# breakout_board_M4.net
KiCad netlist of a schematic drawn in Altium Designer
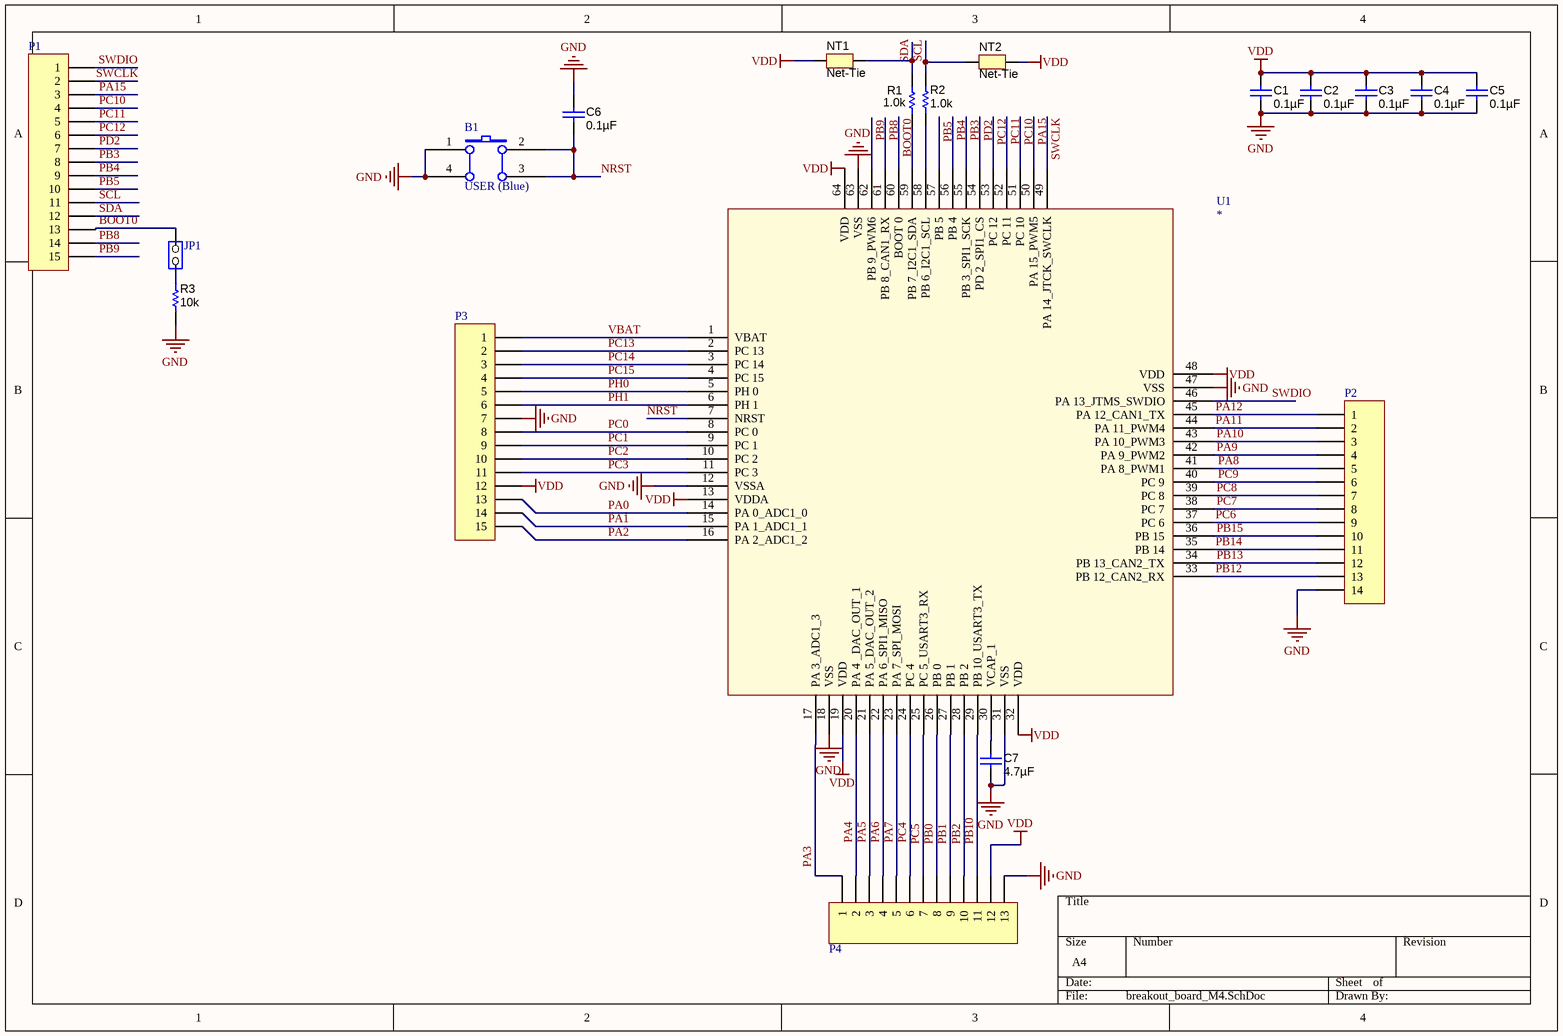
[diagram p0: breakout_board_M4.SchDoc]

(export (version "E")
  (design (tool "Eeschema 10.0.6"))
  (components
    (comp (ref "B1")
      (value "USER (Blue)")
      (footprint "PB-6X6mm-Blue")
      (description "SE PUSHBUTTON")
      (libsource (lib "MB1137") (part "SW PUSHBUTTON"))
    )
    (comp (ref "C1")
      (value "C0603C104K8RACTU")
      (footprint "0603L")
      (description "CAP, CERM, 0.1 µF, 10 V, +/- 10%, X7R, 0603")
      (fields
        (field (name "MANUFACTURER") "Kemet")
        (field (name "VALUEDISPLAYED") "0.1µF")
        (field (name "PUBLISHER") "Texas Instruments")
      )
      (libsource (lib "MDBU014A") (part "C0603C104K8RACTU"))
    )
    (comp (ref "C2")
      (value "C0603C104K8RACTU")
      (footprint "0603L")
      (description "CAP, CERM, 0.1 µF, 10 V, +/- 10%, X7R, 0603")
      (fields
        (field (name "MANUFACTURER") "Kemet")
        (field (name "VALUEDISPLAYED") "0.1µF")
        (field (name "PUBLISHER") "Texas Instruments")
      )
      (libsource (lib "MDBU014A") (part "C0603C104K8RACTU"))
    )
    (comp (ref "C3")
      (value "C0603C104K8RACTU")
      (footprint "0603L")
      (description "CAP, CERM, 0.1 µF, 10 V, +/- 10%, X7R, 0603")
      (fields
        (field (name "MANUFACTURER") "Kemet")
        (field (name "VALUEDISPLAYED") "0.1µF")
        (field (name "PUBLISHER") "Texas Instruments")
      )
      (libsource (lib "MDBU014A") (part "C0603C104K8RACTU"))
    )
    (comp (ref "C4")
      (value "C0603C104K8RACTU")
      (footprint "0603L")
      (description "CAP, CERM, 0.1 µF, 10 V, +/- 10%, X7R, 0603")
      (fields
        (field (name "MANUFACTURER") "Kemet")
        (field (name "VALUEDISPLAYED") "0.1µF")
        (field (name "PUBLISHER") "Texas Instruments")
      )
      (libsource (lib "MDBU014A") (part "C0603C104K8RACTU"))
    )
    (comp (ref "C5")
      (value "C0603C104K8RACTU")
      (footprint "0603L")
      (description "CAP, CERM, 0.1 µF, 10 V, +/- 10%, X7R, 0603")
      (fields
        (field (name "MANUFACTURER") "Kemet")
        (field (name "VALUEDISPLAYED") "0.1µF")
        (field (name "PUBLISHER") "Texas Instruments")
      )
      (libsource (lib "MDBU014A") (part "C0603C104K8RACTU"))
    )
    (comp (ref "C6")
      (value "C0603C104K8RACTU")
      (footprint "0603L")
      (description "CAP, CERM, 0.1 µF, 10 V, +/- 10%, X7R, 0603")
      (fields
        (field (name "MANUFACTURER") "Kemet")
        (field (name "VALUEDISPLAYED") "0.1µF")
        (field (name "PUBLISHER") "Texas Instruments")
      )
      (libsource (lib "MDBU014A") (part "C0603C104K8RACTU"))
    )
    (comp (ref "C7")
      (value "GRM21BR71A475KA73L")
      (footprint "0805L")
      (description "CAP, CERM, 4.7 µF, 10 V, +/- 10%, X7R, 0805")
      (fields
        (field (name "VALUEDISPLAYED") "4.7µF")
        (field (name "MANUFACTURER") "MuRata")
        (field (name "PUBLISHER") "Texas Instruments")
      )
      (libsource (lib "MDBU014A") (part "GRM21BR71A475KA73L"))
    )
    (comp (ref "JP1") (value "~") (footprint "HDR_1x2_2R54_V_M_S") (libsource (lib "MB1137") (part "JP2")))
    (comp (ref "NT1")
      (value "Net-Tie")
      (footprint "Net-Tie_10mil")
      (description "Single point connection between nets.")
      (fields (field (name "SYMBOLCREATOR") "codlsc") (field (name "PUBLISHER") "Texas Instruments"))
      (libsource (lib "MDBU014A") (part "Net-Tie"))
    )
    (comp (ref "NT2")
      (value "Net-Tie")
      (footprint "Net-Tie_10mil")
      (description "Single point connection between nets.")
      (fields (field (name "SYMBOLCREATOR") "codlsc") (field (name "PUBLISHER") "Texas Instruments"))
      (libsource (lib "MDBU014A") (part "Net-Tie"))
    )
    (comp (ref "P1")
      (value "~")
      (footprint "HDR1X15")
      (description "Header, 15-Pin")
      (fields (field (name "PUBLISHER") "Altium Limited"))
      (libsource (lib "Miscellaneous Connectors") (part "Header 15"))
    )
    (comp (ref "P2")
      (value "~")
      (footprint "HDR1X14")
      (description "Header, 14-Pin")
      (fields (field (name "PUBLISHER") "Altium Limited"))
      (libsource (lib "Miscellaneous Connectors") (part "Header 14"))
    )
    (comp (ref "P3")
      (value "~")
      (footprint "HDR1X15")
      (description "Header, 15-Pin")
      (fields (field (name "PUBLISHER") "Altium Limited"))
      (libsource (lib "Miscellaneous Connectors") (part "Header 15"))
    )
    (comp (ref "P4")
      (value "~")
      (footprint "HDR1X13")
      (description "Header, 13-Pin")
      (fields (field (name "PUBLISHER") "Altium Limited"))
      (libsource (lib "Miscellaneous Connectors") (part "Header 13"))
    )
    (comp (ref "R1")
      (value "1.0k")
      (footprint "0603L")
      (description "RES, 1.0 k, 5%, 0.1 W, 0603")
      (fields
        (field (name "PARTNUMBER") "CRCW06031K00JNEA")
        (field (name "MANUFACTURER") "Vishay-Dale")
        (field (name "PUBLISHER") "Texas Instruments")
      )
      (libsource (lib "MDBU014A") (part "CRCW06031K00JNEA"))
    )
    (comp (ref "R2")
      (value "1.0k")
      (footprint "0603L")
      (description "RES, 1.0 k, 5%, 0.1 W, 0603")
      (fields
        (field (name "PARTNUMBER") "CRCW06031K00JNEA")
        (field (name "MANUFACTURER") "Vishay-Dale")
        (field (name "PUBLISHER") "Texas Instruments")
      )
      (libsource (lib "MDBU014A") (part "CRCW06031K00JNEA"))
    )
    (comp (ref "R3")
      (value "10k")
      (footprint "0603L")
      (description "RES, 10 k, 5%, 0.1 W, 0603")
      (fields
        (field (name "PARTNUMBER") "CRCW060310K0JNEA")
        (field (name "MANUFACTURER") "Vishay-Dale")
        (field (name "PUBLISHER") "Texas Instruments")
      )
      (libsource (lib "MDBU014A") (part "CRCW060310K0JNEA"))
    )
    (comp (ref "U1")
      (value "*")
      (footprint "LQFP64-10x10mm")
      (libsource (lib "2017-09-01_10-10-35") (part "STM32F446RE"))
    )
  )
  (nets
    (net (code "1") (name "/BOOT0") (class "Default")
      (node (ref "JP1") (pin "1") (pinfunction "COMMON_1") (pintype "passive"))
      (node (ref "P1") (pin "13") (pinfunction "13_13") (pintype "passive"))
      (node (ref "U1") (pin "60") (pinfunction "BOOT_0_60") (pintype "passive"))
    )
    (net (code "2") (name "/NRST") (class "Default")
      (node (ref "B1") (pin "2") (pinfunction "B0_2") (pintype "passive"))
      (node (ref "B1") (pin "3") (pinfunction "B1_3") (pintype "passive"))
      (node (ref "C6") (pin "2") (pinfunction "2_2") (pintype "passive"))
      (node (ref "U1") (pin "7") (pinfunction "NRST_7") (pintype "passive"))
    )
    (net (code "3") (name "/PA0") (class "Default")
      (node (ref "P3") (pin "13") (pinfunction "13_13") (pintype "passive"))
      (node (ref "U1") (pin "14") (pinfunction "PA_0_ADC1_0_14") (pintype "passive"))
    )
    (net (code "4") (name "/PA1") (class "Default")
      (node (ref "P3") (pin "14") (pinfunction "14_14") (pintype "passive"))
      (node (ref "U1") (pin "15") (pinfunction "PA_1_ADC1_1_15") (pintype "passive"))
    )
    (net (code "5") (name "/PA2") (class "Default")
      (node (ref "P3") (pin "15") (pinfunction "15_15") (pintype "passive"))
      (node (ref "U1") (pin "16") (pinfunction "PA_2_ADC1_2_16") (pintype "passive"))
    )
    (net (code "6") (name "/PA3") (class "Default")
      (node (ref "P4") (pin "1") (pinfunction "1_1") (pintype "passive"))
      (node (ref "U1") (pin "17") (pinfunction "PA_3_ADC1_3_17") (pintype "passive"))
    )
    (net (code "7") (name "/PA4") (class "Default")
      (node (ref "P4") (pin "2") (pinfunction "2_2") (pintype "passive"))
      (node (ref "U1") (pin "20") (pinfunction "PA_4__DAC_OUT_1_20") (pintype "passive"))
    )
    (net (code "8") (name "/PA5") (class "Default")
      (node (ref "P4") (pin "3") (pinfunction "3_3") (pintype "passive"))
      (node (ref "U1") (pin "21") (pinfunction "PA_5_DAC_OUT_2_21") (pintype "passive"))
    )
    (net (code "9") (name "/PA6") (class "Default")
      (node (ref "P4") (pin "4") (pinfunction "4_4") (pintype "passive"))
      (node (ref "U1") (pin "22") (pinfunction "PA_6_SPI1_MISO_22") (pintype "passive"))
    )
    (net (code "10") (name "/PA7") (class "Default")
      (node (ref "P4") (pin "5") (pinfunction "5_5") (pintype "passive"))
      (node (ref "U1") (pin "23") (pinfunction "PA_7_SPI_MOSI_23") (pintype "passive"))
    )
    (net (code "11") (name "/PA8") (class "Default")
      (node (ref "P2") (pin "5") (pinfunction "5_5") (pintype "passive"))
      (node (ref "U1") (pin "41") (pinfunction "PA_8_PWM1_41") (pintype "passive"))
    )
    (net (code "12") (name "/PA9") (class "Default")
      (node (ref "P2") (pin "4") (pinfunction "4_4") (pintype "passive"))
      (node (ref "U1") (pin "42") (pinfunction "PA_9_PWM2_42") (pintype "passive"))
    )
    (net (code "13") (name "/PA10") (class "Default")
      (node (ref "P2") (pin "3") (pinfunction "3_3") (pintype "passive"))
      (node (ref "U1") (pin "43") (pinfunction "PA_10_PWM3_43") (pintype "passive"))
    )
    (net (code "14") (name "/PA11") (class "Default")
      (node (ref "P2") (pin "2") (pinfunction "2_2") (pintype "passive"))
      (node (ref "U1") (pin "44") (pinfunction "PA_11_PWM4_44") (pintype "passive"))
    )
    (net (code "15") (name "/PA12") (class "Default")
      (node (ref "P2") (pin "1") (pinfunction "1_1") (pintype "passive"))
      (node (ref "U1") (pin "45") (pinfunction "PA_12_CAN1_TX_45") (pintype "passive"))
    )
    (net (code "16") (name "/PA15") (class "Default")
      (node (ref "P1") (pin "3") (pinfunction "3_3") (pintype "passive"))
      (node (ref "U1") (pin "50") (pinfunction "PA_15_PWM5_50") (pintype "passive"))
    )
    (net (code "17") (name "/PB0") (class "Default")
      (node (ref "P4") (pin "8") (pinfunction "8_8") (pintype "passive"))
      (node (ref "U1") (pin "26") (pinfunction "PB_0_26") (pintype "passive"))
    )
    (net (code "18") (name "/PB1") (class "Default")
      (node (ref "P4") (pin "9") (pinfunction "9_9") (pintype "passive"))
      (node (ref "U1") (pin "27") (pinfunction "PB_1_27") (pintype "passive"))
    )
    (net (code "19") (name "/PB2") (class "Default")
      (node (ref "P4") (pin "10") (pinfunction "10_10") (pintype "passive"))
      (node (ref "U1") (pin "28") (pinfunction "PB_2_28") (pintype "passive"))
    )
    (net (code "20") (name "/PB3") (class "Default")
      (node (ref "P1") (pin "8") (pinfunction "8_8") (pintype "passive"))
      (node (ref "U1") (pin "55") (pinfunction "PB_3_SPI1_SCK_55") (pintype "passive"))
    )
    (net (code "21") (name "/PB4") (class "Default")
      (node (ref "P1") (pin "9") (pinfunction "9_9") (pintype "passive"))
      (node (ref "U1") (pin "56") (pinfunction "PB_4_56") (pintype "passive"))
    )
    (net (code "22") (name "/PB5") (class "Default")
      (node (ref "P1") (pin "10") (pinfunction "10_10") (pintype "passive"))
      (node (ref "U1") (pin "57") (pinfunction "PB_5_57") (pintype "passive"))
    )
    (net (code "23") (name "/PB8") (class "Default")
      (node (ref "P1") (pin "14") (pinfunction "14_14") (pintype "passive"))
      (node (ref "U1") (pin "61") (pinfunction "PB_8_CAN1_RX_61") (pintype "passive"))
    )
    (net (code "24") (name "/PB9") (class "Default")
      (node (ref "P1") (pin "15") (pinfunction "15_15") (pintype "passive"))
      (node (ref "U1") (pin "62") (pinfunction "PB_9_PWM6_62") (pintype "passive"))
    )
    (net (code "25") (name "/PB10") (class "Default")
      (node (ref "P4") (pin "11") (pinfunction "11_11") (pintype "passive"))
      (node (ref "U1") (pin "29") (pinfunction "PB_10_USART3_TX_29") (pintype "passive"))
    )
    (net (code "26") (name "/PB12") (class "Default")
      (node (ref "P2") (pin "13") (pinfunction "13_13") (pintype "passive"))
      (node (ref "U1") (pin "33") (pinfunction "PB_12_CAN2_RX_33") (pintype "passive"))
    )
    (net (code "27") (name "/PB13") (class "Default")
      (node (ref "P2") (pin "12") (pinfunction "12_12") (pintype "passive"))
      (node (ref "U1") (pin "34") (pinfunction "PB_13_CAN2_TX_34") (pintype "passive"))
    )
    (net (code "28") (name "/PB14") (class "Default")
      (node (ref "P2") (pin "11") (pinfunction "11_11") (pintype "passive"))
      (node (ref "U1") (pin "35") (pinfunction "PB_14_35") (pintype "passive"))
    )
    (net (code "29") (name "/PB15") (class "Default")
      (node (ref "P2") (pin "10") (pinfunction "10_10") (pintype "passive"))
      (node (ref "U1") (pin "36") (pinfunction "PB_15_36") (pintype "passive"))
    )
    (net (code "30") (name "/PC0") (class "Default")
      (node (ref "P3") (pin "8") (pinfunction "8_8") (pintype "passive"))
      (node (ref "U1") (pin "8") (pinfunction "PC_0_8") (pintype "passive"))
    )
    (net (code "31") (name "/PC1") (class "Default")
      (node (ref "P3") (pin "9") (pinfunction "9_9") (pintype "passive"))
      (node (ref "U1") (pin "9") (pinfunction "PC_1_9") (pintype "passive"))
    )
    (net (code "32") (name "/PC2") (class "Default")
      (node (ref "P3") (pin "10") (pinfunction "10_10") (pintype "passive"))
      (node (ref "U1") (pin "10") (pinfunction "PC_2_10") (pintype "passive"))
    )
    (net (code "33") (name "/PC3") (class "Default")
      (node (ref "P3") (pin "11") (pinfunction "11_11") (pintype "passive"))
      (node (ref "U1") (pin "11") (pinfunction "PC_3_11") (pintype "passive"))
    )
    (net (code "34") (name "/PC4") (class "Default")
      (node (ref "P4") (pin "6") (pinfunction "6_6") (pintype "passive"))
      (node (ref "U1") (pin "24") (pinfunction "PC_4_24") (pintype "passive"))
    )
    (net (code "35") (name "/PC5") (class "Default")
      (node (ref "P4") (pin "7") (pinfunction "7_7") (pintype "passive"))
      (node (ref "U1") (pin "25") (pinfunction "PC_5_USART3_RX_25") (pintype "passive"))
    )
    (net (code "36") (name "/PC6") (class "Default")
      (node (ref "P2") (pin "9") (pinfunction "9_9") (pintype "passive"))
      (node (ref "U1") (pin "37") (pinfunction "PC_6_37") (pintype "passive"))
    )
    (net (code "37") (name "/PC7") (class "Default")
      (node (ref "P2") (pin "8") (pinfunction "8_8") (pintype "passive"))
      (node (ref "U1") (pin "38") (pinfunction "PC_7_38") (pintype "passive"))
    )
    (net (code "38") (name "/PC8") (class "Default")
      (node (ref "P2") (pin "7") (pinfunction "7_7") (pintype "passive"))
      (node (ref "U1") (pin "39") (pinfunction "PC_8_39") (pintype "passive"))
    )
    (net (code "39") (name "/PC9") (class "Default")
      (node (ref "P2") (pin "6") (pinfunction "6_6") (pintype "passive"))
      (node (ref "U1") (pin "40") (pinfunction "PC_9_40") (pintype "passive"))
    )
    (net (code "40") (name "/PC10") (class "Default")
      (node (ref "P1") (pin "4") (pinfunction "4_4") (pintype "passive"))
      (node (ref "U1") (pin "51") (pinfunction "PC_10_51") (pintype "passive"))
    )
    (net (code "41") (name "/PC11") (class "Default")
      (node (ref "P1") (pin "5") (pinfunction "5_5") (pintype "passive"))
      (node (ref "U1") (pin "52") (pinfunction "PC_11_52") (pintype "passive"))
    )
    (net (code "42") (name "/PC12") (class "Default")
      (node (ref "P1") (pin "6") (pinfunction "6_6") (pintype "passive"))
      (node (ref "U1") (pin "53") (pinfunction "PC_12_53") (pintype "passive"))
    )
    (net (code "43") (name "/PC13") (class "Default")
      (node (ref "P3") (pin "2") (pinfunction "2_2") (pintype "passive"))
      (node (ref "U1") (pin "2") (pinfunction "PC_13_2") (pintype "passive"))
    )
    (net (code "44") (name "/PC14") (class "Default")
      (node (ref "P3") (pin "3") (pinfunction "3_3") (pintype "passive"))
      (node (ref "U1") (pin "3") (pinfunction "PC_14_3") (pintype "passive"))
    )
    (net (code "45") (name "/PC15") (class "Default")
      (node (ref "P3") (pin "4") (pinfunction "4_4") (pintype "passive"))
      (node (ref "U1") (pin "4") (pinfunction "PC_15_4") (pintype "passive"))
    )
    (net (code "46") (name "/PD2") (class "Default")
      (node (ref "P1") (pin "7") (pinfunction "7_7") (pintype "passive"))
      (node (ref "U1") (pin "54") (pinfunction "PD_2_SPI1_CS_54") (pintype "passive"))
    )
    (net (code "47") (name "/PH0") (class "Default")
      (node (ref "P3") (pin "5") (pinfunction "5_5") (pintype "passive"))
      (node (ref "U1") (pin "5") (pinfunction "PH_0_5") (pintype "passive"))
    )
    (net (code "48") (name "/PH1") (class "Default")
      (node (ref "P3") (pin "6") (pinfunction "6_6") (pintype "passive"))
      (node (ref "U1") (pin "6") (pinfunction "PH_1_6") (pintype "passive"))
    )
    (net (code "49") (name "/SCL") (class "Default")
      (node (ref "NT2") (pin "1") (pinfunction "1_1") (pintype "passive"))
      (node (ref "P1") (pin "11") (pinfunction "11_11") (pintype "passive"))
      (node (ref "R2") (pin "2") (pinfunction "2_2") (pintype "passive"))
    )
    (net (code "50") (name "/SDA") (class "Default")
      (node (ref "NT1") (pin "2") (pinfunction "2_2") (pintype "passive"))
      (node (ref "P1") (pin "12") (pinfunction "12_12") (pintype "passive"))
      (node (ref "R1") (pin "2") (pinfunction "2_2") (pintype "passive"))
    )
    (net (code "51") (name "/SWCLK") (class "Default")
      (node (ref "P1") (pin "2") (pinfunction "2_2") (pintype "passive"))
      (node (ref "U1") (pin "49") (pinfunction "PA_14_JTCK_SWCLK_49") (pintype "passive"))
    )
    (net (code "52") (name "/SWDIO") (class "Default")
      (node (ref "P1") (pin "1") (pinfunction "1_1") (pintype "passive"))
      (node (ref "U1") (pin "46") (pinfunction "PA_13_JTMS_SWDIO_46") (pintype "passive"))
    )
    (net (code "53") (name "/VBAT") (class "Default")
      (node (ref "P3") (pin "1") (pinfunction "1_1") (pintype "passive"))
      (node (ref "U1") (pin "1") (pinfunction "VBAT_1") (pintype "passive"))
    )
    (net (code "54") (name "GND") (class "Default")
      (node (ref "B1") (pin "1") (pinfunction "A0_1") (pintype "passive"))
      (node (ref "B1") (pin "4") (pinfunction "A1_4") (pintype "passive"))
      (node (ref "C1") (pin "2") (pinfunction "2_2") (pintype "passive"))
      (node (ref "C2") (pin "2") (pinfunction "2_2") (pintype "passive"))
      (node (ref "C3") (pin "2") (pinfunction "2_2") (pintype "passive"))
      (node (ref "C4") (pin "2") (pinfunction "2_2") (pintype "passive"))
      (node (ref "C5") (pin "2") (pinfunction "2_2") (pintype "passive"))
      (node (ref "C6") (pin "1") (pinfunction "1_1") (pintype "passive"))
      (node (ref "C7") (pin "1") (pinfunction "1_1") (pintype "passive"))
      (node (ref "P2") (pin "14") (pinfunction "14_14") (pintype "passive"))
      (node (ref "P3") (pin "7") (pinfunction "7_7") (pintype "passive"))
      (node (ref "P4") (pin "13") (pinfunction "13_13") (pintype "passive"))
      (node (ref "R3") (pin "1") (pinfunction "1_1") (pintype "passive"))
      (node (ref "U1") (pin "12") (pinfunction "VSSA_12") (pintype "passive"))
      (node (ref "U1") (pin "18") (pinfunction "VSS_18") (pintype "passive"))
      (node (ref "U1") (pin "31") (pinfunction "VSS_31") (pintype "passive"))
      (node (ref "U1") (pin "47") (pinfunction "VSS_47") (pintype "passive"))
      (node (ref "U1") (pin "63") (pinfunction "VSS_63") (pintype "passive"))
    )
    (net (code "55") (name "Net-(JP1-NO)") (class "Default")
      (node (ref "JP1") (pin "2") (pinfunction "NO_2") (pintype "passive"))
      (node (ref "R3") (pin "2") (pinfunction "2_2") (pintype "passive"))
    )
    (net (code "56") (name "Net-(U1-PB_6_I2C1_SCL)") (class "Default")
      (node (ref "R2") (pin "1") (pinfunction "1_1") (pintype "passive"))
      (node (ref "U1") (pin "58") (pinfunction "PB_6_I2C1_SCL_58") (pintype "passive"))
    )
    (net (code "57") (name "Net-(U1-PB_7_I2C1_SDA)") (class "Default")
      (node (ref "R1") (pin "1") (pinfunction "1_1") (pintype "passive"))
      (node (ref "U1") (pin "59") (pinfunction "PB_7_I2C1_SDA_59") (pintype "passive"))
    )
    (net (code "58") (name "Net-(U1-VCAP_1)") (class "Default")
      (node (ref "C7") (pin "2") (pinfunction "2_2") (pintype "passive"))
      (node (ref "U1") (pin "30") (pinfunction "VCAP_1_30") (pintype "passive"))
    )
    (net (code "59") (name "VDD") (class "Default")
      (node (ref "C1") (pin "1") (pinfunction "1_1") (pintype "passive"))
      (node (ref "C2") (pin "1") (pinfunction "1_1") (pintype "passive"))
      (node (ref "C3") (pin "1") (pinfunction "1_1") (pintype "passive"))
      (node (ref "C4") (pin "1") (pinfunction "1_1") (pintype "passive"))
      (node (ref "C5") (pin "1") (pinfunction "1_1") (pintype "passive"))
      (node (ref "NT1") (pin "1") (pinfunction "1_1") (pintype "passive"))
      (node (ref "NT2") (pin "2") (pinfunction "2_2") (pintype "passive"))
      (node (ref "P3") (pin "12") (pinfunction "12_12") (pintype "passive"))
      (node (ref "P4") (pin "12") (pinfunction "12_12") (pintype "passive"))
      (node (ref "U1") (pin "13") (pinfunction "VDDA_13") (pintype "passive"))
      (node (ref "U1") (pin "19") (pinfunction "VDD_19") (pintype "passive"))
      (node (ref "U1") (pin "32") (pinfunction "VDD_32") (pintype "passive"))
      (node (ref "U1") (pin "48") (pinfunction "VDD_48") (pintype "passive"))
      (node (ref "U1") (pin "64") (pinfunction "VDD_64") (pintype "passive"))
    )
  )
)
